# lat_stm_zybo_rev.net
KiCad netlist of a schematic drawn in EAGLE
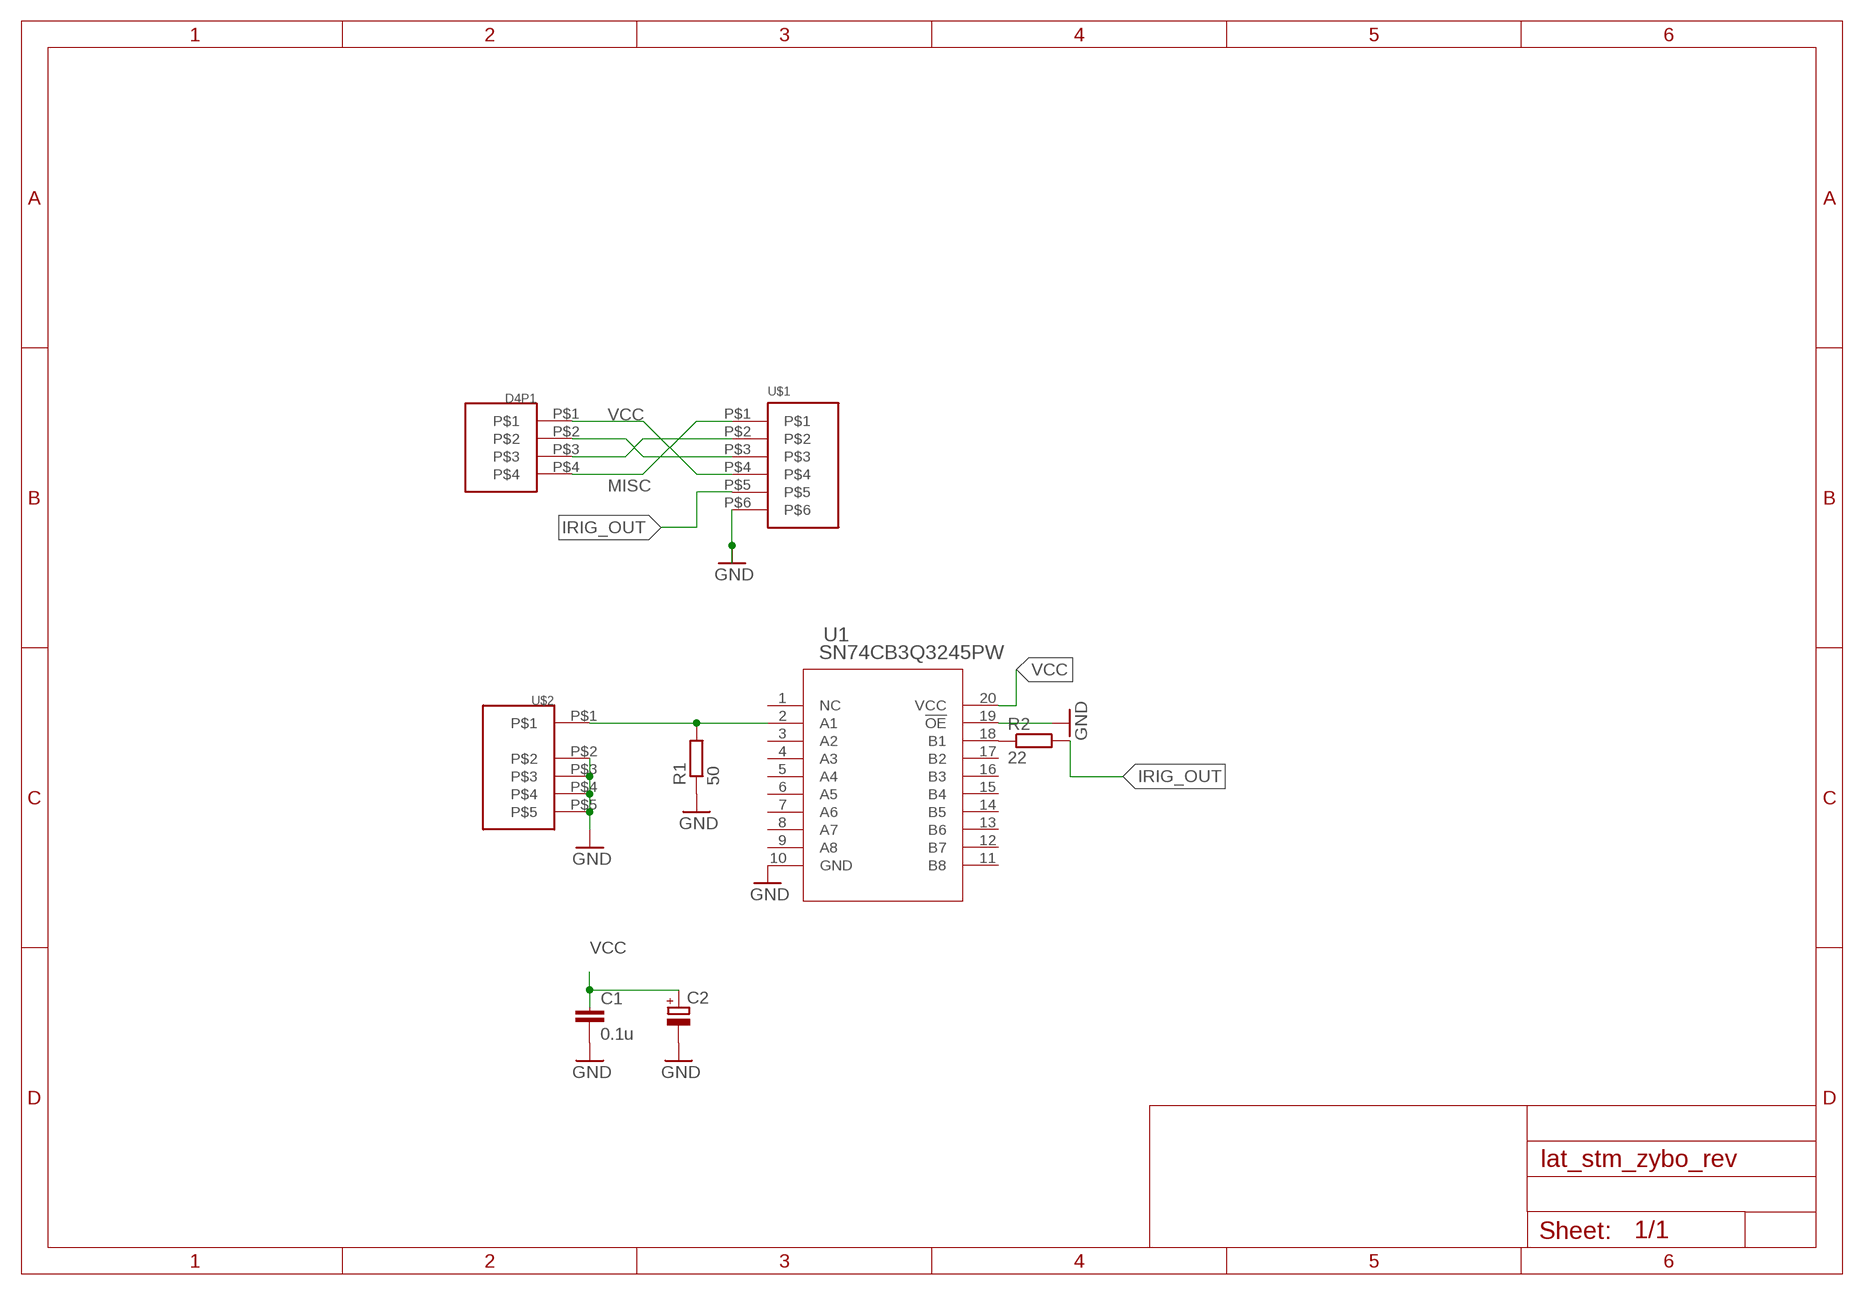
[diagram p0: schematic, sheet 1]

(export (version "E")
  (design (tool "Eeschema 10.0.6"))
  (components
    (comp (ref "C1")
      (value "0.1u")
      (footprint "eagle-import:C0603")
      (libsource (lib "eagle-import") (part "C-EUC0603"))
    )
    (comp (ref "C2")
      (value "CPOL-EUE2,5-6E")
      (footprint "eagle-import:E2,5-6E")
      (libsource (lib "eagle-import") (part "CPOL-EUE2,5-6E"))
    )
    (comp (ref "D4P1")
      (value "DF1E-4P")
      (footprint "eagle-import:DF1E-4P")
      (libsource (lib "eagle-import") (part "DF1E-4P"))
    )
    (comp (ref "R1")
      (value "50")
      (footprint "eagle-import:R0603")
      (libsource (lib "eagle-import") (part "R-EU_R0603"))
    )
    (comp (ref "R2")
      (value "22")
      (footprint "eagle-import:R0603")
      (libsource (lib "eagle-import") (part "R-EU_R0603"))
    )
    (comp (ref "U$1")
      (value "DF1E-6P")
      (footprint "eagle-import:DF1E-6P")
      (libsource (lib "eagle-import") (part "DF1E-6P"))
    )
    (comp (ref "U$2")
      (value "546-4049")
      (footprint "eagle-import:546-4049")
      (libsource (lib "eagle-import") (part "546-4049"))
    )
    (comp (ref "U1")
      (value "SN74CB3Q3245PW")
      (footprint "eagle-import:PW20")
      (fields
        (field (name "GENERIC_PART_NUMBER") "SN74CB3Q3245")
        (field (name "MANUFACTURER") "Texas Instruments")
      )
      (libsource (lib "eagle-import") (part "SN74CB3Q3245PW"))
    )
  )
  (nets
    (net (code "1") (name "/MISC") (class "Default")
      (node (ref "D4P1") (pin "P$4") (pinfunction "P$4_P$4") (pintype "bidirectional"))
      (node (ref "U$1") (pin "P$1") (pinfunction "P$1_P$1") (pintype "bidirectional"))
    )
    (net (code "2") (name "GND") (class "Default")
      (node (ref "C1") (pin "2") (pinfunction "2_2") (pintype "passive"))
      (node (ref "C2") (pin "-") (pinfunction "-_-") (pintype "passive"))
      (node (ref "R1") (pin "1") (pinfunction "1_1") (pintype "passive"))
      (node (ref "U$1") (pin "P$6") (pinfunction "P$6_P$6") (pintype "bidirectional"))
      (node (ref "U$2") (pin "P$2") (pinfunction "P$2_P$2") (pintype "bidirectional"))
      (node (ref "U$2") (pin "P$3") (pinfunction "P$3_P$3") (pintype "bidirectional"))
      (node (ref "U$2") (pin "P$4") (pinfunction "P$4_P$4") (pintype "bidirectional"))
      (node (ref "U$2") (pin "P$5") (pinfunction "P$5_P$5") (pintype "bidirectional"))
      (node (ref "U1") (pin "10") (pinfunction "GND_10") (pintype "power_in"))
      (node (ref "U1") (pin "19") (pinfunction "~{OE}_19") (pintype "input"))
    )
    (net (code "3") (name "IRIG_OUT") (class "Default")
      (node (ref "R2") (pin "2") (pinfunction "2_2") (pintype "passive"))
      (node (ref "U$1") (pin "P$5") (pinfunction "P$5_P$5") (pintype "bidirectional"))
    )
    (net (code "4") (name "Net-(D4P1-PadP$2)") (class "Default")
      (node (ref "D4P1") (pin "P$2") (pinfunction "P$2_P$2") (pintype "bidirectional"))
      (node (ref "U$1") (pin "P$3") (pinfunction "P$3_P$3") (pintype "bidirectional"))
    )
    (net (code "5") (name "Net-(D4P1-PadP$3)") (class "Default")
      (node (ref "D4P1") (pin "P$3") (pinfunction "P$3_P$3") (pintype "bidirectional"))
      (node (ref "U$1") (pin "P$2") (pinfunction "P$2_P$2") (pintype "bidirectional"))
    )
    (net (code "6") (name "Net-(U1-A1)") (class "Default")
      (node (ref "R1") (pin "2") (pinfunction "2_2") (pintype "passive"))
      (node (ref "U$2") (pin "P$1") (pinfunction "P$1_P$1") (pintype "bidirectional"))
      (node (ref "U1") (pin "2") (pinfunction "A1_2") (pintype "bidirectional"))
    )
    (net (code "7") (name "Net-(U1-B1)") (class "Default")
      (node (ref "R2") (pin "1") (pinfunction "1_1") (pintype "passive"))
      (node (ref "U1") (pin "18") (pinfunction "B1_18") (pintype "bidirectional"))
    )
    (net (code "8") (name "VCC") (class "Default")
      (node (ref "C1") (pin "1") (pinfunction "1_1") (pintype "passive"))
      (node (ref "C2") (pin "+") (pinfunction "+_+") (pintype "passive"))
      (node (ref "D4P1") (pin "P$1") (pinfunction "P$1_P$1") (pintype "bidirectional"))
      (node (ref "U$1") (pin "P$4") (pinfunction "P$4_P$4") (pintype "bidirectional"))
      (node (ref "U1") (pin "20") (pinfunction "VCC_20") (pintype "power_in"))
    )
    (net (code "9") (name "unconnected-(U1-A2-Pad3)") (class "Default")
      (node (ref "U1") (pin "3") (pinfunction "A2_3") (pintype "bidirectional"))
    )
    (net (code "10") (name "unconnected-(U1-A3-Pad4)") (class "Default")
      (node (ref "U1") (pin "4") (pinfunction "A3_4") (pintype "bidirectional"))
    )
    (net (code "11") (name "unconnected-(U1-A4-Pad5)") (class "Default")
      (node (ref "U1") (pin "5") (pinfunction "A4_5") (pintype "bidirectional"))
    )
    (net (code "12") (name "unconnected-(U1-A5-Pad6)") (class "Default")
      (node (ref "U1") (pin "6") (pinfunction "A5_6") (pintype "bidirectional"))
    )
    (net (code "13") (name "unconnected-(U1-A6-Pad7)") (class "Default")
      (node (ref "U1") (pin "7") (pinfunction "A6_7") (pintype "bidirectional"))
    )
    (net (code "14") (name "unconnected-(U1-A7-Pad8)") (class "Default")
      (node (ref "U1") (pin "8") (pinfunction "A7_8") (pintype "bidirectional"))
    )
    (net (code "15") (name "unconnected-(U1-A8-Pad9)") (class "Default")
      (node (ref "U1") (pin "9") (pinfunction "A8_9") (pintype "bidirectional"))
    )
    (net (code "16") (name "unconnected-(U1-B2-Pad17)") (class "Default")
      (node (ref "U1") (pin "17") (pinfunction "B2_17") (pintype "bidirectional"))
    )
    (net (code "17") (name "unconnected-(U1-B3-Pad16)") (class "Default")
      (node (ref "U1") (pin "16") (pinfunction "B3_16") (pintype "bidirectional"))
    )
    (net (code "18") (name "unconnected-(U1-B4-Pad15)") (class "Default")
      (node (ref "U1") (pin "15") (pinfunction "B4_15") (pintype "bidirectional"))
    )
    (net (code "19") (name "unconnected-(U1-B5-Pad14)") (class "Default")
      (node (ref "U1") (pin "14") (pinfunction "B5_14") (pintype "bidirectional"))
    )
    (net (code "20") (name "unconnected-(U1-B6-Pad13)") (class "Default")
      (node (ref "U1") (pin "13") (pinfunction "B6_13") (pintype "bidirectional"))
    )
    (net (code "21") (name "unconnected-(U1-B7-Pad12)") (class "Default")
      (node (ref "U1") (pin "12") (pinfunction "B7_12") (pintype "bidirectional"))
    )
    (net (code "22") (name "unconnected-(U1-B8-Pad11)") (class "Default")
      (node (ref "U1") (pin "11") (pinfunction "B8_11") (pintype "bidirectional"))
    )
    (net (code "23") (name "unconnected-(U1-NC-Pad1)") (class "Default")
      (node (ref "U1") (pin "1") (pinfunction "NC_1") (pintype "passive"))
    )
  )
)
